# ZigBee.net
KiCad netlist of a schematic drawn in Altium Designer
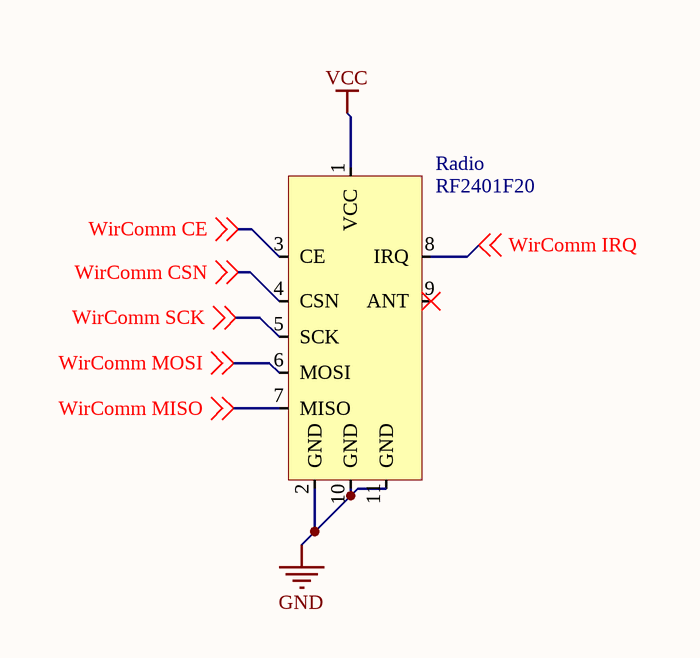
[diagram p0: ZigBee.SchDoc]

(export (version "E")
  (design (tool "Eeschema 10.0.6"))
  (components
    (comp (ref "Radio")
      (value "RF2401F20")
      (footprint "RF2401F20")
      (libsource (lib "HGCDLibrary") (part "RF2401F20"))
    )
  )
  (nets
    (net (code "1") (name "GND") (class "Default")
      (node (ref "Radio") (pin "10") (pinfunction "GND_10") (pintype "passive"))
      (node (ref "Radio") (pin "11") (pinfunction "GND_11") (pintype "passive"))
      (node (ref "Radio") (pin "2") (pinfunction "GND_2") (pintype "passive"))
    )
    (net (code "2") (name "VCC") (class "Default")
      (node (ref "Radio") (pin "1") (pinfunction "VCC_1") (pintype "passive"))
    )
    (net (code "3") (name "WirComm CE") (class "Default")
      (node (ref "Radio") (pin "3") (pinfunction "CE_3") (pintype "input"))
    )
    (net (code "4") (name "WirComm CSN") (class "Default")
      (node (ref "Radio") (pin "4") (pinfunction "CSN_4") (pintype "input"))
    )
    (net (code "5") (name "WirComm IRQ") (class "Default")
      (node (ref "Radio") (pin "8") (pinfunction "IRQ_8") (pintype "output"))
    )
    (net (code "6") (name "WirComm MISO") (class "Default")
      (node (ref "Radio") (pin "7") (pinfunction "MISO_7") (pintype "bidirectional"))
    )
    (net (code "7") (name "WirComm MOSI") (class "Default")
      (node (ref "Radio") (pin "6") (pinfunction "MOSI_6") (pintype "bidirectional"))
    )
    (net (code "8") (name "WirComm SCK") (class "Default")
      (node (ref "Radio") (pin "5") (pinfunction "SCK_5") (pintype "bidirectional"))
    )
    (net (code "9") (name "unconnected-(Radio-ANT-Pad9)") (class "Default")
      (node (ref "Radio") (pin "9") (pinfunction "ANT_9") (pintype "output+no_connect"))
    )
  )
)
